# MCU.net
KiCad netlist of a schematic drawn in Altium Designer
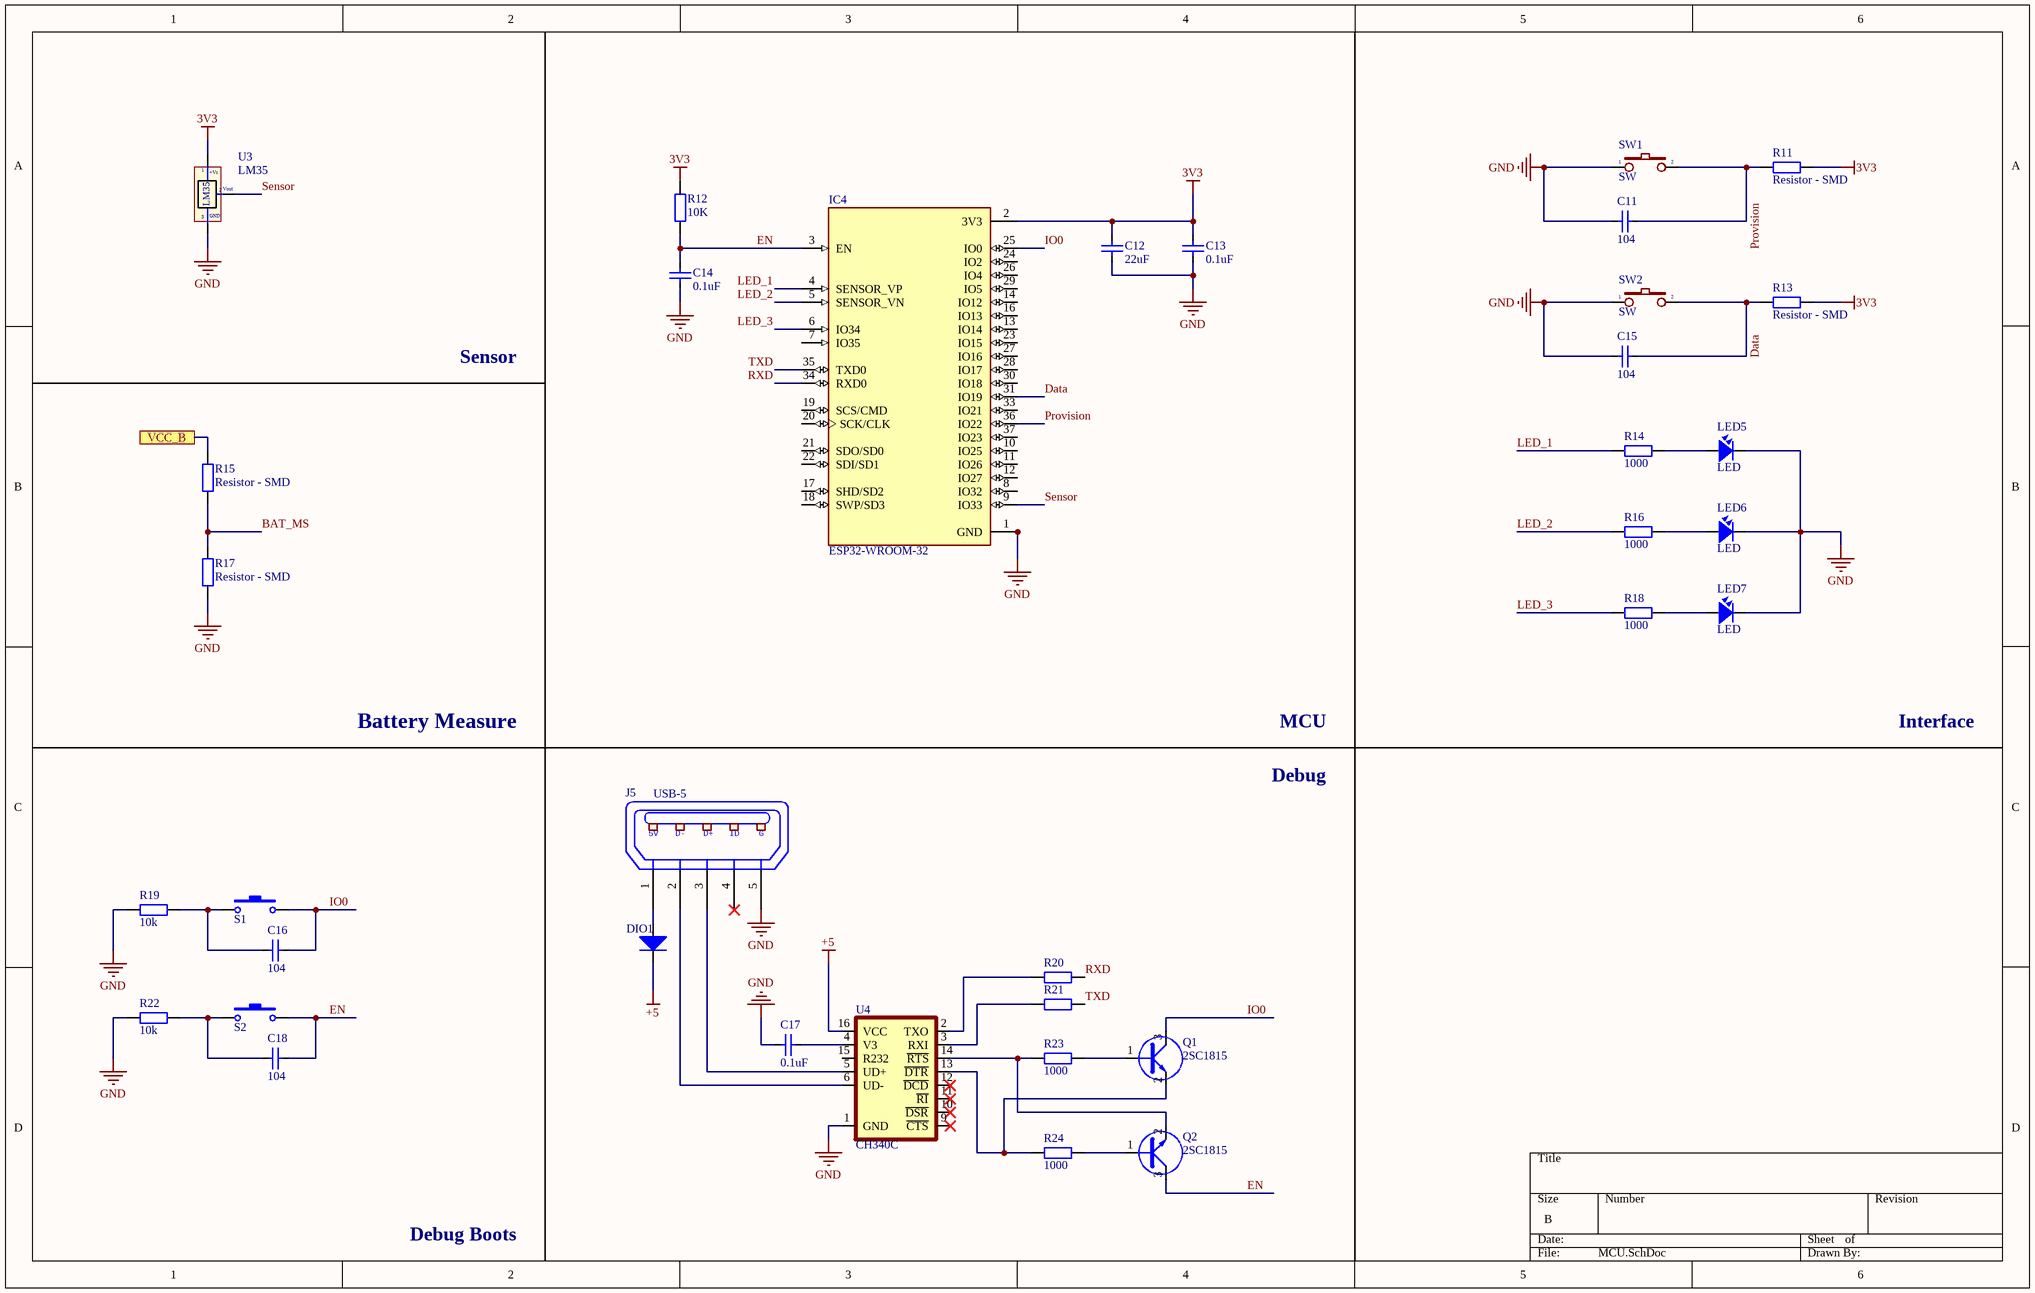
[diagram p0: MCU.SchDoc]

(export (version "E")
  (design (tool "Eeschema 10.0.6"))
  (components
    (comp (ref "C11")
      (value "104")
      (footprint "CAP_0805")
      (description "Capacitor")
      (fields (field (name "PUBLISHER") "Altium Limited"))
      (libsource (lib "My Library") (part "CapSMD"))
    )
    (comp (ref "C12")
      (value "22uF")
      (footprint "CAP_0805")
      (description "Capacitor")
      (fields (field (name "PUBLISHER") "Altium Limited"))
      (libsource (lib "My Library") (part "CapSMD"))
    )
    (comp (ref "C13")
      (value "0.1uF")
      (footprint "CAP_0805")
      (description "Capacitor")
      (fields (field (name "PUBLISHER") "Altium Limited"))
      (libsource (lib "My Library") (part "CapSMD"))
    )
    (comp (ref "C14")
      (value "0.1uF")
      (footprint "CAP_0805")
      (description "Capacitor")
      (fields (field (name "PUBLISHER") "Altium Limited"))
      (libsource (lib "My Library") (part "CapSMD"))
    )
    (comp (ref "C15")
      (value "104")
      (footprint "CAP_0805")
      (description "Capacitor")
      (fields (field (name "PUBLISHER") "Altium Limited"))
      (libsource (lib "My Library") (part "CapSMD"))
    )
    (comp (ref "C16")
      (value "104")
      (footprint "CAP_0805")
      (description "Capacitor")
      (fields (field (name "PUBLISHER") "Altium Limited"))
      (libsource (lib "My Library") (part "CapSMD"))
    )
    (comp (ref "C17")
      (value "0.1uF")
      (footprint "CAP_0805")
      (description "Capacitor")
      (fields (field (name "PUBLISHER") "Altium Limited"))
      (libsource (lib "My Library") (part "CapSMD"))
    )
    (comp (ref "C18")
      (value "104")
      (footprint "CAP_0805")
      (description "Capacitor")
      (fields (field (name "PUBLISHER") "Altium Limited"))
      (libsource (lib "My Library") (part "CapSMD"))
    )
    (comp (ref "DIO1")
      (value "Diode SMD")
      (footprint "DIO-214AC(SMA)")
      (description "Default Diode")
      (fields (field (name "PUBLISHER") "Altium Limited"))
      (libsource (lib "My Library") (part "Diode SMD"))
    )
    (comp (ref "IC4")
      (value "ESP32-WROOM-32")
      (footprint "MODULE_ESP32-WROOM-32")
      (description "Bluetooth, WiFi Transceiver Module 2.4GHz ~ 2.5GHz Surface Mount")
      (fields (field (name "MF") "Espressif Systems") (field (name "DIGI-KEY_PART_NUMBER") "1904-1010-1-ND"))
      (libsource (lib "My Library") (part "ESP32-WROOM-32"))
    )
    (comp (ref "J5")
      (value "USB-5")
      (footprint "USB-M1")
      (fields
        (field (name "MANUFACTURER") "FCI")
        (field (name "MANUFACTURER PART NUMBER") "10118193-0001LF")
        (field (name ".CREATOR") "MM")
        (field (name ".CHECKED PCB") "RF")
        (field (name ".CHECKED SCH") "MM")
      )
      (libsource (lib "My Library") (part "USB-5"))
    )
    (comp (ref "LED5")
      (value "LED")
      (footprint "LED-0805-Red")
      (description "LED Single colour Green and Red")
      (libsource (lib "My Library") (part "LED"))
    )
    (comp (ref "LED6")
      (value "LED")
      (footprint "LED-0805-Red")
      (description "LED Single colour Green and Red")
      (libsource (lib "My Library") (part "LED"))
    )
    (comp (ref "LED7")
      (value "LED")
      (footprint "LED-0805-Red")
      (description "LED Single colour Green and Red")
      (libsource (lib "My Library") (part "LED"))
    )
    (comp (ref "Q1")
      (value "2SC1815")
      (footprint "SOT23D")
      (description "NPN 600mW, ECB")
      (libsource (lib "") (part "C1815_1"))
    )
    (comp (ref "Q2")
      (value "2SC1815")
      (footprint "SOT23D")
      (description "NPN 600mW, ECB")
      (libsource (lib "My Library") (part "C1815"))
    )
    (comp (ref "R11")
      (value "Resistor - SMD")
      (footprint "RES-SMD-0805")
      (description "Resistor SMD")
      (fields
        (field (name "MANUFACTURER") "Generic Components")
        (field (name "PUBLISHER") "Altium Hobart Technology Centre")
      )
      (libsource (lib "My Library") (part "Resistor - SMD"))
    )
    (comp (ref "R12")
      (value "10K")
      (footprint "RES-SMD-0805")
      (description "Resistor SMD")
      (fields
        (field (name "MANUFACTURER") "Generic Components")
        (field (name "PUBLISHER") "Altium Hobart Technology Centre")
      )
      (libsource (lib "My Library") (part "Resistor - SMD"))
    )
    (comp (ref "R13")
      (value "Resistor - SMD")
      (footprint "RES-SMD-0805")
      (description "Resistor SMD")
      (fields
        (field (name "MANUFACTURER") "Generic Components")
        (field (name "PUBLISHER") "Altium Hobart Technology Centre")
      )
      (libsource (lib "My Library") (part "Resistor - SMD"))
    )
    (comp (ref "R14")
      (value "1000")
      (footprint "RES-SMD-0805")
      (description "Resistor SMD")
      (fields
        (field (name "MANUFACTURER") "Generic Components")
        (field (name "PUBLISHER") "Altium Hobart Technology Centre")
      )
      (libsource (lib "My Library") (part "Resistor - SMD"))
    )
    (comp (ref "R15")
      (value "Resistor - SMD")
      (footprint "RES-SMD-0805")
      (description "Resistor SMD")
      (fields
        (field (name "MANUFACTURER") "Generic Components")
        (field (name "PUBLISHER") "Altium Hobart Technology Centre")
      )
      (libsource (lib "My Library") (part "Resistor - SMD"))
    )
    (comp (ref "R16")
      (value "1000")
      (footprint "RES-SMD-0805")
      (description "Resistor SMD")
      (fields
        (field (name "MANUFACTURER") "Generic Components")
        (field (name "PUBLISHER") "Altium Hobart Technology Centre")
      )
      (libsource (lib "My Library") (part "Resistor - SMD"))
    )
    (comp (ref "R17")
      (value "Resistor - SMD")
      (footprint "RES-SMD-0805")
      (description "Resistor SMD")
      (fields
        (field (name "MANUFACTURER") "Generic Components")
        (field (name "PUBLISHER") "Altium Hobart Technology Centre")
      )
      (libsource (lib "My Library") (part "Resistor - SMD"))
    )
    (comp (ref "R18")
      (value "1000")
      (footprint "RES-SMD-0805")
      (description "Resistor SMD")
      (fields
        (field (name "MANUFACTURER") "Generic Components")
        (field (name "PUBLISHER") "Altium Hobart Technology Centre")
      )
      (libsource (lib "My Library") (part "Resistor - SMD"))
    )
    (comp (ref "R19")
      (value "10k")
      (footprint "RES-SMD-0805")
      (description "Resistor SMD")
      (fields
        (field (name "MANUFACTURER") "Generic Components")
        (field (name "PUBLISHER") "Altium Hobart Technology Centre")
      )
      (libsource (lib "My Library") (part "Resistor - SMD"))
    )
    (comp (ref "R20")
      (value "0R")
      (footprint "RES-SMD-0805")
      (description "Resistor SMD")
      (fields
        (field (name "MANUFACTURER") "Generic Components")
        (field (name "PUBLISHER") "Altium Hobart Technology Centre")
      )
      (libsource (lib "My Library") (part "Resistor - SMD"))
    )
    (comp (ref "R21")
      (value "0R")
      (footprint "RES-SMD-0805")
      (description "Resistor SMD")
      (fields
        (field (name "MANUFACTURER") "Generic Components")
        (field (name "PUBLISHER") "Altium Hobart Technology Centre")
      )
      (libsource (lib "My Library") (part "Resistor - SMD"))
    )
    (comp (ref "R22")
      (value "10k")
      (footprint "RES-SMD-0805")
      (description "Resistor SMD")
      (fields
        (field (name "MANUFACTURER") "Generic Components")
        (field (name "PUBLISHER") "Altium Hobart Technology Centre")
      )
      (libsource (lib "My Library") (part "Resistor - SMD"))
    )
    (comp (ref "R23")
      (value "1000")
      (footprint "RES-SMD-0805")
      (description "Resistor SMD")
      (fields
        (field (name "MANUFACTURER") "Generic Components")
        (field (name "PUBLISHER") "Altium Hobart Technology Centre")
      )
      (libsource (lib "My Library") (part "Resistor - SMD"))
    )
    (comp (ref "R24")
      (value "1000")
      (footprint "RES-SMD-0805")
      (description "Resistor SMD")
      (fields
        (field (name "MANUFACTURER") "Generic Components")
        (field (name "PUBLISHER") "Altium Hobart Technology Centre")
      )
      (libsource (lib "My Library") (part "Resistor - SMD"))
    )
    (comp (ref "S1")
      (value "SW-SMD")
      (footprint "SW-SMD")
      (description "Switch")
      (fields (field (name "PUBLISHER") "Altium Limited"))
      (libsource (lib "My Library") (part "SW-SMD"))
    )
    (comp (ref "S2")
      (value "SW-SMD")
      (footprint "SW-SMD")
      (description "Switch")
      (fields (field (name "PUBLISHER") "Altium Limited"))
      (libsource (lib "My Library") (part "SW-SMD"))
    )
    (comp (ref "SW1")
      (value "SW")
      (footprint "SW2")
      (description "Switch button 2 pin")
      (libsource (lib "My Library") (part "SW2"))
    )
    (comp (ref "SW2")
      (value "SW")
      (footprint "SW2")
      (description "Switch button 2 pin")
      (libsource (lib "My Library") (part "SW2"))
    )
    (comp (ref "U3")
      (value "LM35")
      (footprint "QTO-92")
      (description "Teminal")
      (libsource (lib "My Library") (part "LM35"))
    )
    (comp (ref "U4")
      (value "CH340C")
      (footprint "SOP-16")
      (description "USB to serial chip CH340")
      (fields (field (name "MF") "WCH"))
      (libsource (lib "My Library") (part "CH340C"))
    )
  )
  (nets
    (net (code "1") (name "+5") (class "Default")
      (node (ref "DIO1") (pin "2") (pinfunction "K_2") (pintype "passive"))
      (node (ref "U4") (pin "16") (pinfunction "VCC_16") (pintype "bidirectional"))
    )
    (net (code "2") (name "/BAT_MS") (class "Default")
      (node (ref "R15") (pin "2") (pinfunction "2_2") (pintype "passive"))
      (node (ref "R17") (pin "1") (pinfunction "1_1") (pintype "passive"))
    )
    (net (code "3") (name "/Data") (class "Default")
      (node (ref "C15") (pin "2") (pinfunction "2_2") (pintype "passive"))
      (node (ref "IC4") (pin "31") (pinfunction "IO19_31") (pintype "bidirectional"))
      (node (ref "R13") (pin "2") (pinfunction "2_2") (pintype "passive"))
      (node (ref "SW2") (pin "2") (pinfunction "2_2") (pintype "passive"))
    )
    (net (code "4") (name "/EN") (class "Default")
      (node (ref "C14") (pin "2") (pinfunction "2_2") (pintype "passive"))
      (node (ref "C18") (pin "2") (pinfunction "2_2") (pintype "passive"))
      (node (ref "IC4") (pin "3") (pinfunction "EN_3") (pintype "input"))
      (node (ref "Q2") (pin "3") (pinfunction "C_3") (pintype "passive"))
      (node (ref "R12") (pin "2") (pinfunction "2_2") (pintype "passive"))
      (node (ref "S2") (pin "2") (pinfunction "2_2") (pintype "passive"))
    )
    (net (code "5") (name "/IO0") (class "Default")
      (node (ref "C16") (pin "2") (pinfunction "2_2") (pintype "passive"))
      (node (ref "IC4") (pin "25") (pinfunction "IO0_25") (pintype "bidirectional"))
      (node (ref "Q1") (pin "3") (pinfunction "C_3") (pintype "passive"))
      (node (ref "S1") (pin "2") (pinfunction "2_2") (pintype "passive"))
    )
    (net (code "6") (name "/LED_1") (class "Default")
      (node (ref "IC4") (pin "4") (pinfunction "SENSOR_VP_4") (pintype "input"))
      (node (ref "R14") (pin "1") (pinfunction "1_1") (pintype "passive"))
    )
    (net (code "7") (name "/LED_2") (class "Default")
      (node (ref "IC4") (pin "5") (pinfunction "SENSOR_VN_5") (pintype "input"))
      (node (ref "R16") (pin "1") (pinfunction "1_1") (pintype "passive"))
    )
    (net (code "8") (name "/LED_3") (class "Default")
      (node (ref "IC4") (pin "6") (pinfunction "IO34_6") (pintype "input"))
      (node (ref "R18") (pin "1") (pinfunction "1_1") (pintype "passive"))
    )
    (net (code "9") (name "/Provision") (class "Default")
      (node (ref "C11") (pin "2") (pinfunction "2_2") (pintype "passive"))
      (node (ref "IC4") (pin "36") (pinfunction "IO22_36") (pintype "bidirectional"))
      (node (ref "R11") (pin "2") (pinfunction "2_2") (pintype "passive"))
      (node (ref "SW1") (pin "2") (pinfunction "2_2") (pintype "passive"))
    )
    (net (code "10") (name "/RXD") (class "Default")
      (node (ref "IC4") (pin "34") (pinfunction "RXD0_34") (pintype "bidirectional"))
      (node (ref "R20") (pin "1") (pinfunction "1_1") (pintype "passive"))
    )
    (net (code "11") (name "/Sensor") (class "Default")
      (node (ref "IC4") (pin "9") (pinfunction "IO33_9") (pintype "bidirectional"))
      (node (ref "U3") (pin "2") (pinfunction "Vout_2") (pintype "passive"))
    )
    (net (code "12") (name "/TXD") (class "Default")
      (node (ref "IC4") (pin "35") (pinfunction "TXD0_35") (pintype "bidirectional"))
      (node (ref "R21") (pin "1") (pinfunction "1_1") (pintype "passive"))
    )
    (net (code "13") (name "/VCC_B") (class "Default")
      (node (ref "R15") (pin "1") (pinfunction "1_1") (pintype "passive"))
    )
    (net (code "14") (name "3V3") (class "Default")
      (node (ref "C12") (pin "2") (pinfunction "2_2") (pintype "passive"))
      (node (ref "C13") (pin "2") (pinfunction "2_2") (pintype "passive"))
      (node (ref "IC4") (pin "2") (pinfunction "3V3_2") (pintype "power_in"))
      (node (ref "R11") (pin "1") (pinfunction "1_1") (pintype "passive"))
      (node (ref "R12") (pin "1") (pinfunction "1_1") (pintype "passive"))
      (node (ref "R13") (pin "1") (pinfunction "1_1") (pintype "passive"))
      (node (ref "U3") (pin "1") (pinfunction "+Vs_1") (pintype "passive"))
    )
    (net (code "15") (name "GND") (class "Default")
      (node (ref "C11") (pin "1") (pinfunction "1_1") (pintype "passive"))
      (node (ref "C12") (pin "1") (pinfunction "1_1") (pintype "passive"))
      (node (ref "C13") (pin "1") (pinfunction "1_1") (pintype "passive"))
      (node (ref "C14") (pin "1") (pinfunction "1_1") (pintype "passive"))
      (node (ref "C15") (pin "1") (pinfunction "1_1") (pintype "passive"))
      (node (ref "C17") (pin "1") (pinfunction "1_1") (pintype "passive"))
      (node (ref "IC4") (pin "1") (pinfunction "GND_1") (pintype "power_in"))
      (node (ref "IC4") (pin "15") (pinfunction "GND_15") (pintype "power_in"))
      (node (ref "IC4") (pin "38") (pinfunction "GND_38") (pintype "power_in"))
      (node (ref "IC4") (pin "39_1") (pinfunction "GND_39_1") (pintype "power_in"))
      (node (ref "IC4") (pin "39_10") (pinfunction "GND_39_10") (pintype "power_in"))
      (node (ref "IC4") (pin "39_11") (pinfunction "GND_39_11") (pintype "power_in"))
      (node (ref "IC4") (pin "39_12") (pinfunction "GND_39_12") (pintype "power_in"))
      (node (ref "IC4") (pin "39_13") (pinfunction "GND_39_13") (pintype "power_in"))
      (node (ref "IC4") (pin "39_14") (pinfunction "GND_39_14") (pintype "power_in"))
      (node (ref "IC4") (pin "39_15") (pinfunction "GND_39_15") (pintype "power_in"))
      (node (ref "IC4") (pin "39_16") (pinfunction "GND_39_16") (pintype "power_in"))
      (node (ref "IC4") (pin "39_17") (pinfunction "GND_39_17") (pintype "power_in"))
      (node (ref "IC4") (pin "39_18") (pinfunction "GND_39_18") (pintype "power_in"))
      (node (ref "IC4") (pin "39_19") (pinfunction "GND_39_19") (pintype "power_in"))
      (node (ref "IC4") (pin "39_2") (pinfunction "GND_39_2") (pintype "power_in"))
      (node (ref "IC4") (pin "39_20") (pinfunction "GND_39_20") (pintype "power_in"))
      (node (ref "IC4") (pin "39_21") (pinfunction "GND_39_21") (pintype "power_in"))
      (node (ref "IC4") (pin "39_3") (pinfunction "GND_39_3") (pintype "power_in"))
      (node (ref "IC4") (pin "39_4") (pinfunction "GND_39_4") (pintype "power_in"))
      (node (ref "IC4") (pin "39_5") (pinfunction "GND_39_5") (pintype "power_in"))
      (node (ref "IC4") (pin "39_6") (pinfunction "GND_39_6") (pintype "power_in"))
      (node (ref "IC4") (pin "39_7") (pinfunction "GND_39_7") (pintype "power_in"))
      (node (ref "IC4") (pin "39_8") (pinfunction "GND_39_8") (pintype "power_in"))
      (node (ref "IC4") (pin "39_9") (pinfunction "GND_39_9") (pintype "power_in"))
      (node (ref "J5") (pin "5") (pinfunction "P5_5") (pintype "passive"))
      (node (ref "LED5") (pin "2") (pinfunction "2_2") (pintype "passive"))
      (node (ref "LED6") (pin "2") (pinfunction "2_2") (pintype "passive"))
      (node (ref "LED7") (pin "2") (pinfunction "2_2") (pintype "passive"))
      (node (ref "R17") (pin "2") (pinfunction "2_2") (pintype "passive"))
      (node (ref "R19") (pin "2") (pinfunction "2_2") (pintype "passive"))
      (node (ref "R22") (pin "2") (pinfunction "2_2") (pintype "passive"))
      (node (ref "SW1") (pin "1") (pinfunction "1_1") (pintype "passive"))
      (node (ref "SW2") (pin "1") (pinfunction "1_1") (pintype "passive"))
      (node (ref "U3") (pin "3") (pinfunction "-_3") (pintype "passive"))
      (node (ref "U4") (pin "1") (pinfunction "GND_1") (pintype "bidirectional"))
    )
    (net (code "16") (name "Net-(C16-Pad1)") (class "Default")
      (node (ref "C16") (pin "1") (pinfunction "1_1") (pintype "passive"))
      (node (ref "R19") (pin "1") (pinfunction "1_1") (pintype "passive"))
      (node (ref "S1") (pin "1") (pinfunction "1_1") (pintype "passive"))
    )
    (net (code "17") (name "Net-(C18-Pad1)") (class "Default")
      (node (ref "C18") (pin "1") (pinfunction "1_1") (pintype "passive"))
      (node (ref "R22") (pin "1") (pinfunction "1_1") (pintype "passive"))
      (node (ref "S2") (pin "1") (pinfunction "1_1") (pintype "passive"))
    )
    (net (code "18") (name "Net-(DIO1-A)") (class "Default")
      (node (ref "DIO1") (pin "1") (pinfunction "A_1") (pintype "passive"))
      (node (ref "J5") (pin "1") (pinfunction "P1_1") (pintype "passive"))
    )
    (net (code "19") (name "Net-(J5-P2)") (class "Default")
      (node (ref "J5") (pin "2") (pinfunction "P2_2") (pintype "passive"))
      (node (ref "U4") (pin "6") (pinfunction "UD-_6") (pintype "bidirectional"))
    )
    (net (code "20") (name "Net-(J5-P3)") (class "Default")
      (node (ref "J5") (pin "3") (pinfunction "P3_3") (pintype "passive"))
      (node (ref "U4") (pin "5") (pinfunction "UD+_5") (pintype "bidirectional"))
    )
    (net (code "21") (name "Net-(LED5-Pad1)") (class "Default")
      (node (ref "LED5") (pin "1") (pinfunction "1_1") (pintype "passive"))
      (node (ref "R14") (pin "2") (pinfunction "2_2") (pintype "passive"))
    )
    (net (code "22") (name "Net-(LED6-Pad1)") (class "Default")
      (node (ref "LED6") (pin "1") (pinfunction "1_1") (pintype "passive"))
      (node (ref "R16") (pin "2") (pinfunction "2_2") (pintype "passive"))
    )
    (net (code "23") (name "Net-(LED7-Pad1)") (class "Default")
      (node (ref "LED7") (pin "1") (pinfunction "1_1") (pintype "passive"))
      (node (ref "R18") (pin "2") (pinfunction "2_2") (pintype "passive"))
    )
    (net (code "24") (name "Net-(Q1-B)") (class "Default")
      (node (ref "Q1") (pin "1") (pinfunction "B_1") (pintype "passive"))
      (node (ref "R23") (pin "1") (pinfunction "1_1") (pintype "passive"))
    )
    (net (code "25") (name "Net-(Q1-E)") (class "Default")
      (node (ref "Q1") (pin "2") (pinfunction "E_2") (pintype "passive"))
      (node (ref "R24") (pin "2") (pinfunction "2_2") (pintype "passive"))
      (node (ref "U4") (pin "13") (pinfunction "~{DTR}_13") (pintype "bidirectional"))
    )
    (net (code "26") (name "Net-(Q2-B)") (class "Default")
      (node (ref "Q2") (pin "1") (pinfunction "B_1") (pintype "passive"))
      (node (ref "R24") (pin "1") (pinfunction "1_1") (pintype "passive"))
    )
    (net (code "27") (name "Net-(Q2-E)") (class "Default")
      (node (ref "Q2") (pin "2") (pinfunction "E_2") (pintype "passive"))
      (node (ref "R23") (pin "2") (pinfunction "2_2") (pintype "passive"))
      (node (ref "U4") (pin "14") (pinfunction "~{RTS}_14") (pintype "bidirectional"))
    )
    (net (code "28") (name "Net-(U4-RXI)") (class "Default")
      (node (ref "R21") (pin "2") (pinfunction "2_2") (pintype "passive"))
      (node (ref "U4") (pin "3") (pinfunction "RXI_3") (pintype "bidirectional"))
    )
    (net (code "29") (name "Net-(U4-TXO)") (class "Default")
      (node (ref "R20") (pin "2") (pinfunction "2_2") (pintype "passive"))
      (node (ref "U4") (pin "2") (pinfunction "TXO_2") (pintype "bidirectional"))
    )
    (net (code "30") (name "Net-(U4-V3)") (class "Default")
      (node (ref "C17") (pin "2") (pinfunction "2_2") (pintype "passive"))
      (node (ref "U4") (pin "4") (pinfunction "V3_4") (pintype "bidirectional"))
    )
    (net (code "31") (name "unconnected-(IC4-IO2-Pad24)") (class "Default")
      (node (ref "IC4") (pin "24") (pinfunction "IO2_24") (pintype "bidirectional"))
    )
    (net (code "32") (name "unconnected-(IC4-IO4-Pad26)") (class "Default")
      (node (ref "IC4") (pin "26") (pinfunction "IO4_26") (pintype "bidirectional"))
    )
    (net (code "33") (name "unconnected-(IC4-IO5-Pad29)") (class "Default")
      (node (ref "IC4") (pin "29") (pinfunction "IO5_29") (pintype "bidirectional"))
    )
    (net (code "34") (name "unconnected-(IC4-IO12-Pad14)") (class "Default")
      (node (ref "IC4") (pin "14") (pinfunction "IO12_14") (pintype "bidirectional"))
    )
    (net (code "35") (name "unconnected-(IC4-IO13-Pad16)") (class "Default")
      (node (ref "IC4") (pin "16") (pinfunction "IO13_16") (pintype "bidirectional"))
    )
    (net (code "36") (name "unconnected-(IC4-IO14-Pad13)") (class "Default")
      (node (ref "IC4") (pin "13") (pinfunction "IO14_13") (pintype "bidirectional"))
    )
    (net (code "37") (name "unconnected-(IC4-IO15-Pad23)") (class "Default")
      (node (ref "IC4") (pin "23") (pinfunction "IO15_23") (pintype "bidirectional"))
    )
    (net (code "38") (name "unconnected-(IC4-IO16-Pad27)") (class "Default")
      (node (ref "IC4") (pin "27") (pinfunction "IO16_27") (pintype "bidirectional"))
    )
    (net (code "39") (name "unconnected-(IC4-IO17-Pad28)") (class "Default")
      (node (ref "IC4") (pin "28") (pinfunction "IO17_28") (pintype "bidirectional"))
    )
    (net (code "40") (name "unconnected-(IC4-IO18-Pad30)") (class "Default")
      (node (ref "IC4") (pin "30") (pinfunction "IO18_30") (pintype "bidirectional"))
    )
    (net (code "41") (name "unconnected-(IC4-IO21-Pad33)") (class "Default")
      (node (ref "IC4") (pin "33") (pinfunction "IO21_33") (pintype "bidirectional"))
    )
    (net (code "42") (name "unconnected-(IC4-IO23-Pad37)") (class "Default")
      (node (ref "IC4") (pin "37") (pinfunction "IO23_37") (pintype "bidirectional"))
    )
    (net (code "43") (name "unconnected-(IC4-IO25-Pad10)") (class "Default")
      (node (ref "IC4") (pin "10") (pinfunction "IO25_10") (pintype "bidirectional"))
    )
    (net (code "44") (name "unconnected-(IC4-IO26-Pad11)") (class "Default")
      (node (ref "IC4") (pin "11") (pinfunction "IO26_11") (pintype "bidirectional"))
    )
    (net (code "45") (name "unconnected-(IC4-IO27-Pad12)") (class "Default")
      (node (ref "IC4") (pin "12") (pinfunction "IO27_12") (pintype "bidirectional"))
    )
    (net (code "46") (name "unconnected-(IC4-IO32-Pad8)") (class "Default")
      (node (ref "IC4") (pin "8") (pinfunction "IO32_8") (pintype "bidirectional"))
    )
    (net (code "47") (name "unconnected-(IC4-IO35-Pad7)") (class "Default")
      (node (ref "IC4") (pin "7") (pinfunction "IO35_7") (pintype "input"))
    )
    (net (code "48") (name "unconnected-(IC4-SCK{slash}CLK-Pad20)") (class "Default")
      (node (ref "IC4") (pin "20") (pinfunction "SCK/CLK_20") (pintype "bidirectional"))
    )
    (net (code "49") (name "unconnected-(IC4-SCS{slash}CMD-Pad19)") (class "Default")
      (node (ref "IC4") (pin "19") (pinfunction "SCS/CMD_19") (pintype "bidirectional"))
    )
    (net (code "50") (name "unconnected-(IC4-SDI{slash}SD1-Pad22)") (class "Default")
      (node (ref "IC4") (pin "22") (pinfunction "SDI/SD1_22") (pintype "bidirectional"))
    )
    (net (code "51") (name "unconnected-(IC4-SDO{slash}SD0-Pad21)") (class "Default")
      (node (ref "IC4") (pin "21") (pinfunction "SDO/SD0_21") (pintype "bidirectional"))
    )
    (net (code "52") (name "unconnected-(IC4-SHD{slash}SD2-Pad17)") (class "Default")
      (node (ref "IC4") (pin "17") (pinfunction "SHD/SD2_17") (pintype "bidirectional"))
    )
    (net (code "53") (name "unconnected-(IC4-SWP{slash}SD3-Pad18)") (class "Default")
      (node (ref "IC4") (pin "18") (pinfunction "SWP/SD3_18") (pintype "bidirectional"))
    )
    (net (code "54") (name "unconnected-(J5-P4-Pad4)") (class "Default")
      (node (ref "J5") (pin "4") (pinfunction "P4_4") (pintype "passive+no_connect"))
    )
    (net (code "55") (name "unconnected-(U4-R232-Pad15)") (class "Default")
      (node (ref "U4") (pin "15") (pinfunction "R232_15") (pintype "bidirectional"))
    )
    (net (code "56") (name "unconnected-(U4-~{CTS}-Pad9)") (class "Default")
      (node (ref "U4") (pin "9") (pinfunction "~{CTS}_9") (pintype "bidirectional+no_connect"))
    )
    (net (code "57") (name "unconnected-(U4-~{DCD}-Pad12)") (class "Default")
      (node (ref "U4") (pin "12") (pinfunction "~{DCD}_12") (pintype "bidirectional+no_connect"))
    )
    (net (code "58") (name "unconnected-(U4-~{DSR}-Pad10)") (class "Default")
      (node (ref "U4") (pin "10") (pinfunction "~{DSR}_10") (pintype "bidirectional+no_connect"))
    )
    (net (code "59") (name "unconnected-(U4-~{RI}-Pad11)") (class "Default")
      (node (ref "U4") (pin "11") (pinfunction "~{RI}_11") (pintype "bidirectional+no_connect"))
    )
  )
)
